# schematic.net
KiCad netlist of a schematic drawn in Altium Designer
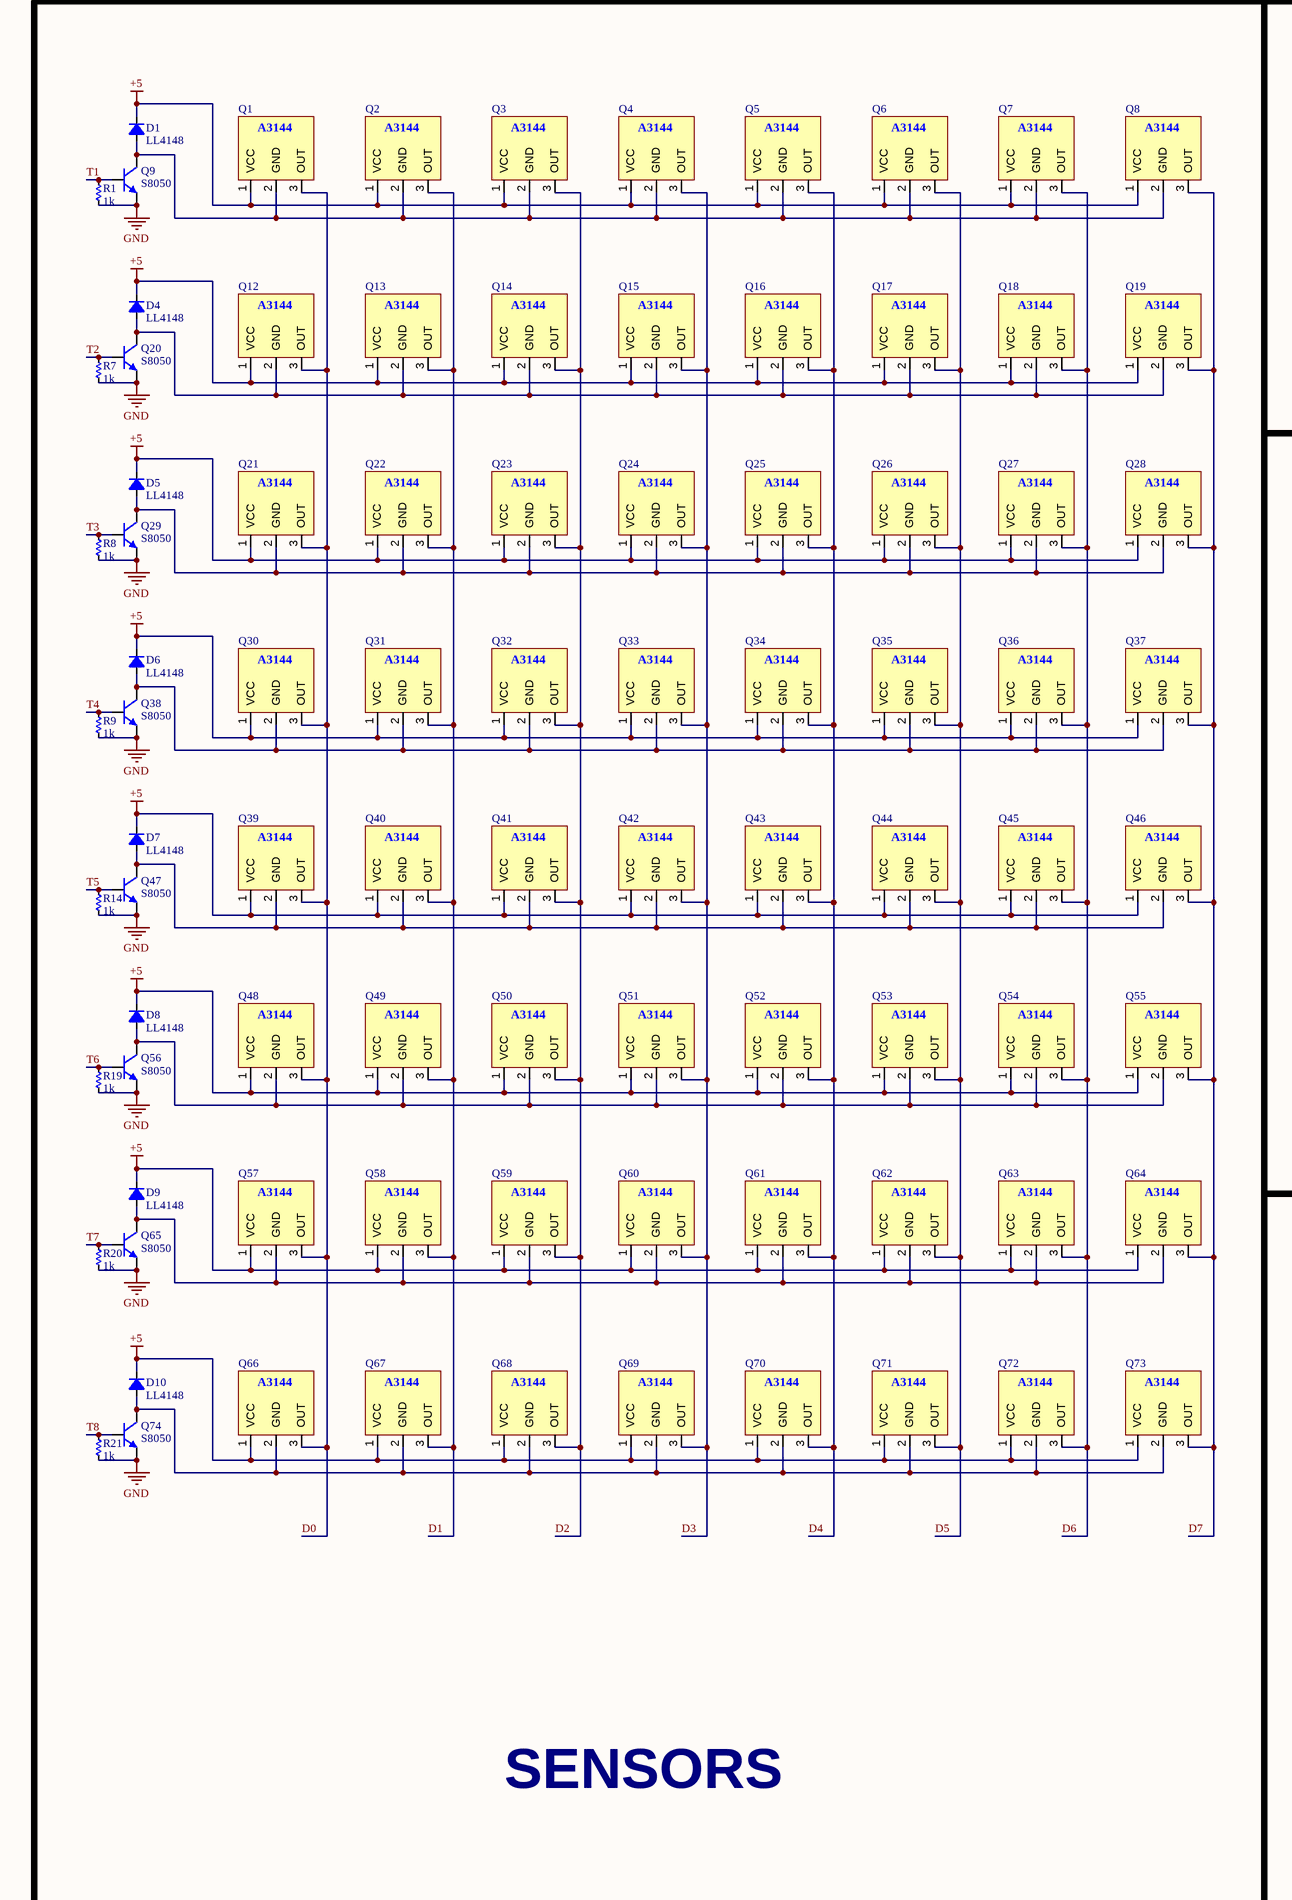
[diagram p0: schematic.SchDoc, left]
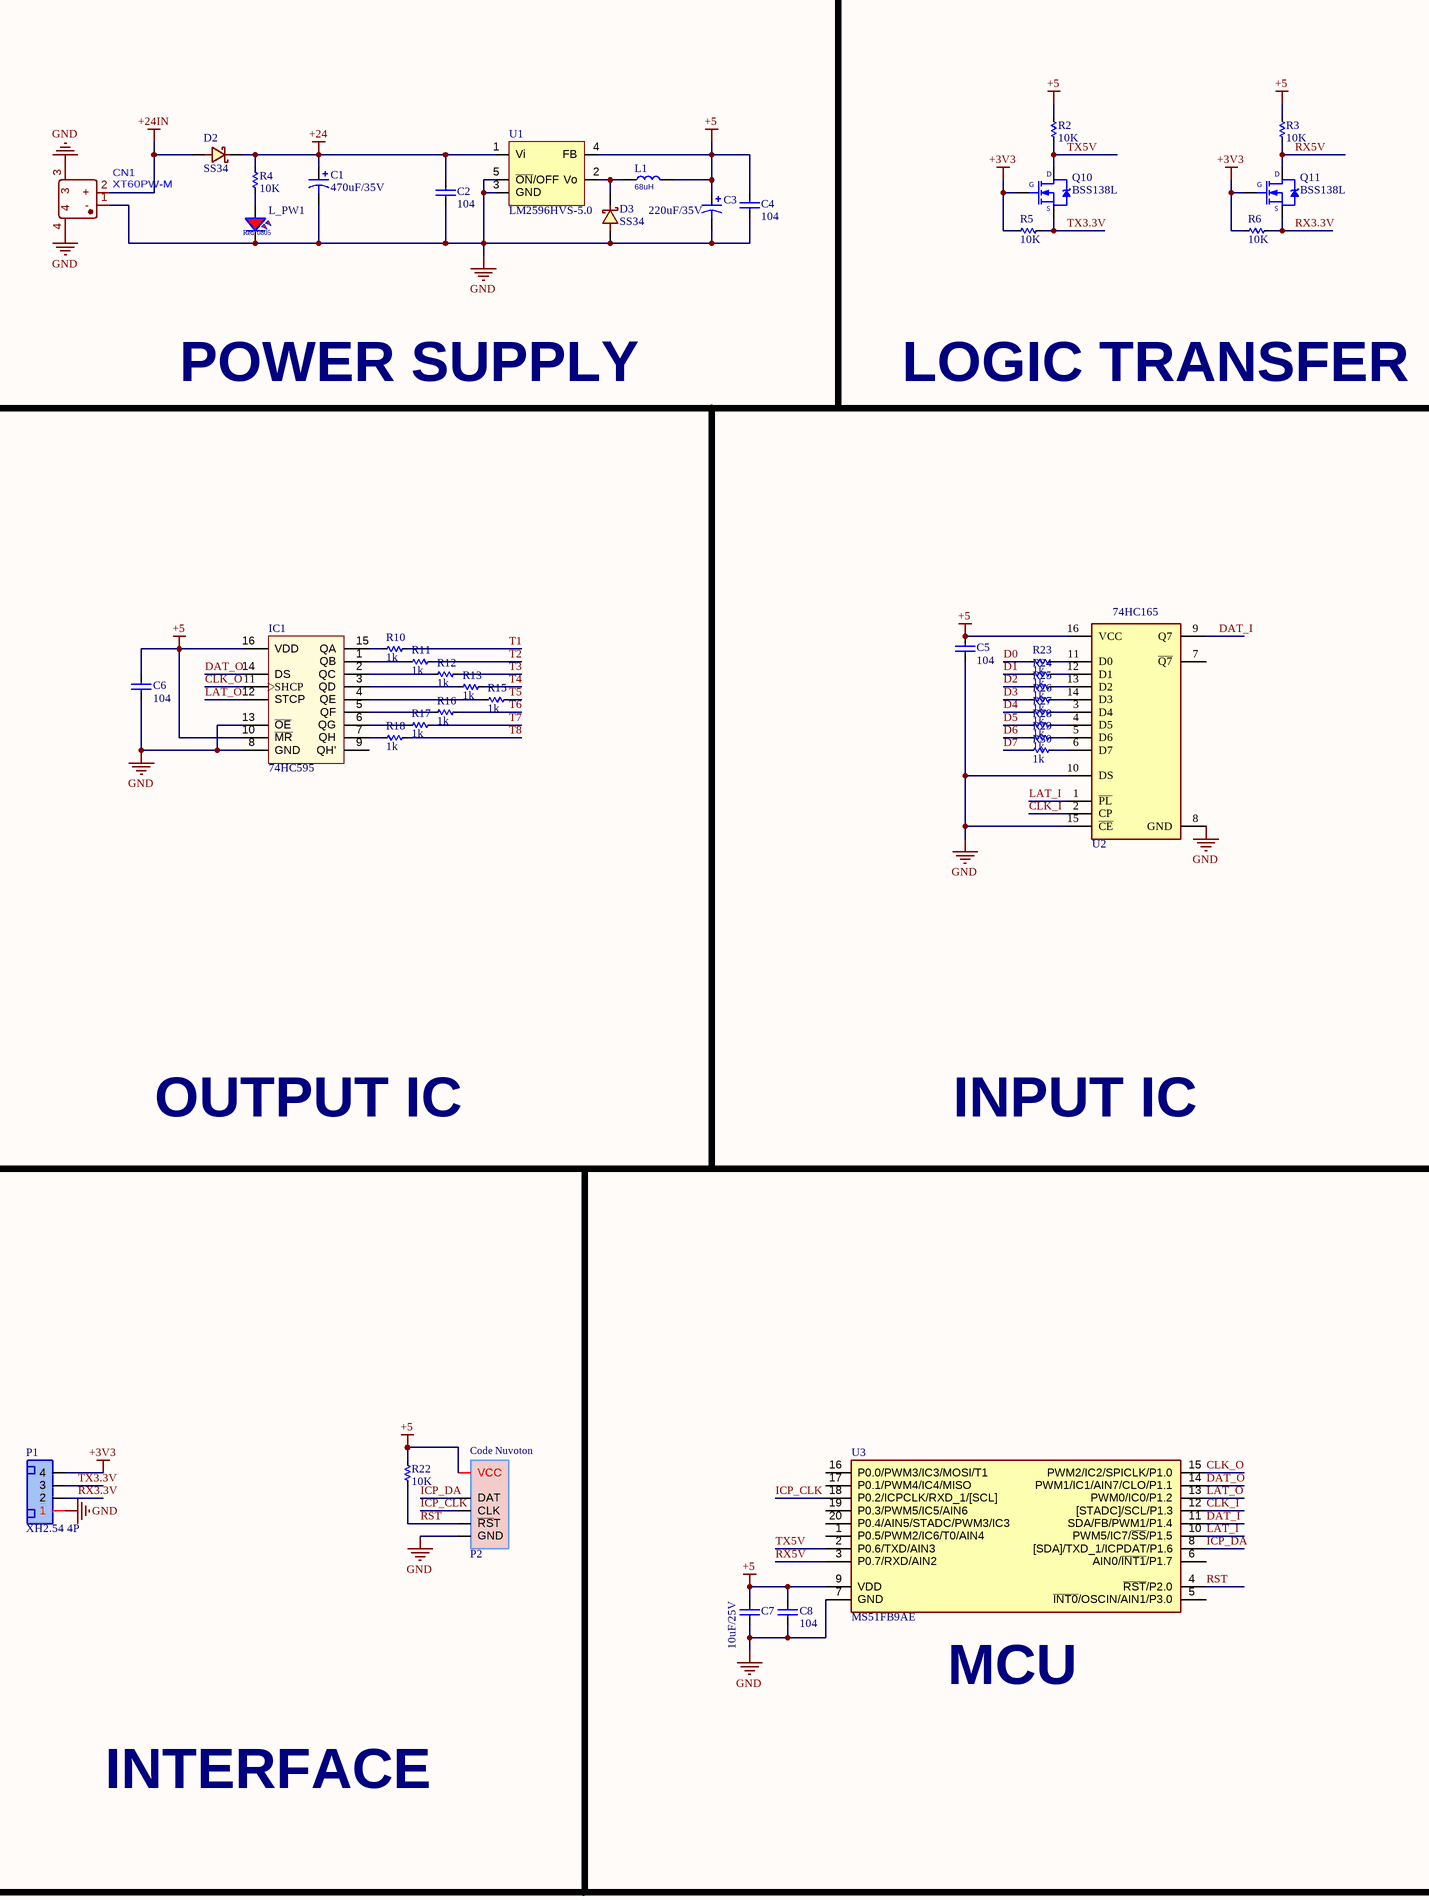
[diagram p1: schematic.SchDoc, right]

(export (version "E")
  (design (tool "Eeschema 10.0.6"))
  (components
    (comp (ref "C1")
      (value "470uF/35V")
      (footprint "C8X12mm")
      (description "Polarized Capacitor (Axial) 470uF 35V")
      (libsource (lib "RD Integrated_Library") (part "Cap Pol 470uF/35V"))
    )
    (comp (ref "C2")
      (value "104")
      (footprint "C_0805_SMD")
      (description "Cap SMD 0805 104-100nF-0.1uF 50V")
      (libsource (lib "RD Integrated_Library") (part "Cap 0805 104 100nF"))
    )
    (comp (ref "C3")
      (value "220uF/35V")
      (footprint "C8X12mm")
      (description "Polarized Capacitor (Axial) 220uF 35V")
      (libsource (lib "RD Integrated_Library") (part "Cap Pol 220uF/35V"))
    )
    (comp (ref "C4")
      (value "104")
      (footprint "C_0805_SMD")
      (description "Cap SMD 0805 104-100nF-0.1uF 50V")
      (libsource (lib "RD Integrated_Library") (part "Cap 0805 104 100nF"))
    )
    (comp (ref "C5")
      (value "104")
      (footprint "C_0805_SMD")
      (description "Cap SMD 0805 104-100nF-0.1uF 50V")
      (libsource (lib "RD Integrated_Library") (part "Cap 0805 104 100nF"))
    )
    (comp (ref "C6")
      (value "104")
      (footprint "C_0805_SMD")
      (description "Cap SMD 0805 104-100nF-0.1uF 50V")
      (libsource (lib "RD Integrated_Library") (part "Cap 0805 104 100nF"))
    )
    (comp (ref "C7")
      (value "10uF/25V")
      (footprint "C_0805_SMD")
      (description "Cap SMD 0805 10uF")
      (libsource (lib "RD Integrated_Library") (part "Cap 0805 10uF 25V"))
    )
    (comp (ref "C8")
      (value "104")
      (footprint "C_0805_SMD")
      (description "Cap SMD 0805 104-100nF-0.1uF 50V")
      (libsource (lib "RD Integrated_Library") (part "Cap 0805 104 100nF"))
    )
    (comp (ref "CN1")
      (value "XT60PW-M")
      (footprint "CONN-TH_XT60PW-M")
      (libsource (lib "Dlib") (part "XT60PW-M"))
    )
    (comp (ref "D1")
      (value "LL4148")
      (footprint "SOD80C_MFG")
      (description "0.2A, 100V, SOD80")
      (fields (field (name "DESIGNED BY") "Nhox"))
      (libsource (lib "RD Integrated_Library") (part "LL4148"))
    )
    (comp (ref "D2")
      (value "SS34")
      (footprint "D_SMA")
      (description "Surface-Mount Schottky Barrier Rectifier")
      (libsource (lib "RD Integrated_Library") (part "SS34-SMA"))
    )
    (comp (ref "D3")
      (value "SS34")
      (footprint "D_SMA")
      (description "Surface-Mount Schottky Barrier Rectifier")
      (libsource (lib "RD Integrated_Library") (part "SS34-SMA"))
    )
    (comp (ref "D4")
      (value "LL4148")
      (footprint "SOD80C_MFG")
      (description "0.2A, 100V, SOD80")
      (fields (field (name "DESIGNED BY") "Nhox"))
      (libsource (lib "RD Integrated_Library") (part "LL4148"))
    )
    (comp (ref "D5")
      (value "LL4148")
      (footprint "SOD80C_MFG")
      (description "0.2A, 100V, SOD80")
      (fields (field (name "DESIGNED BY") "Nhox"))
      (libsource (lib "RD Integrated_Library") (part "LL4148"))
    )
    (comp (ref "D6")
      (value "LL4148")
      (footprint "SOD80C_MFG")
      (description "0.2A, 100V, SOD80")
      (fields (field (name "DESIGNED BY") "Nhox"))
      (libsource (lib "RD Integrated_Library") (part "LL4148"))
    )
    (comp (ref "D7")
      (value "LL4148")
      (footprint "SOD80C_MFG")
      (description "0.2A, 100V, SOD80")
      (fields (field (name "DESIGNED BY") "Nhox"))
      (libsource (lib "RD Integrated_Library") (part "LL4148"))
    )
    (comp (ref "D8")
      (value "LL4148")
      (footprint "SOD80C_MFG")
      (description "0.2A, 100V, SOD80")
      (fields (field (name "DESIGNED BY") "Nhox"))
      (libsource (lib "RD Integrated_Library") (part "LL4148"))
    )
    (comp (ref "D9")
      (value "LL4148")
      (footprint "SOD80C_MFG")
      (description "0.2A, 100V, SOD80")
      (fields (field (name "DESIGNED BY") "Nhox"))
      (libsource (lib "RD Integrated_Library") (part "LL4148"))
    )
    (comp (ref "D10")
      (value "LL4148")
      (footprint "SOD80C_MFG")
      (description "0.2A, 100V, SOD80")
      (fields (field (name "DESIGNED BY") "Nhox"))
      (libsource (lib "RD Integrated_Library") (part "LL4148"))
    )
    (comp (ref "IC1")
      (value "74HC595")
      (footprint "SO_16")
      (description "Shift Register Single 8-Bit Serial to Serial/Parallel 16-Pin SOIC T/R")
      (fields (field (name "DESIGNED BY") "nhox"))
      (libsource (lib "RD Integrated_Library") (part "74HC595 SMD SO16"))
    )
    (comp (ref "L1")
      (value "68uH")
      (footprint "CDRH127")
      (description "CDRH127 Cuộn Cảm Dán SMD 1280-680 68uH 3.2A")
      (libsource (lib "RD Integrated_Library") (part "IND CDRH127 1280-680 68uH"))
    )
    (comp (ref "L_PW1")
      (value "LED RED")
      (footprint "LED 0805 Red")
      (description "LED 0805 SMD RED")
      (fields (field (name "DESIGNED BY") "TranLuyen"))
      (libsource (lib "RD Integrated_Library") (part "LED 0805 RED"))
    )
    (comp (ref "P1")
      (value "XH2.54 4P")
      (footprint "XH2.54_4P_RA")
      (description "XH2.54 RA")
      (libsource (lib "RD Integrated_Library") (part "XH2.54_4P_RA"))
    )
    (comp (ref "P2")
      (value "Nuvoton")
      (footprint "Header Code Nuvoton 2.54 6P")
      (description "Header 6-5Pin")
      (libsource (lib "RD Integrated_Library") (part "Header Code Nuvoton"))
    )
    (comp (ref "Q1")
      (value "A3144")
      (footprint "QTO-92")
      (description "Sensitive Hall Effect Switches for High-Temperature Operation 4.5-24V")
      (libsource (lib "RD Integrated_Library") (part "hall sensor A3144"))
    )
    (comp (ref "Q2")
      (value "A3144")
      (footprint "QTO-92")
      (description "Sensitive Hall Effect Switches for High-Temperature Operation 4.5-24V")
      (libsource (lib "RD Integrated_Library") (part "hall sensor A3144"))
    )
    (comp (ref "Q3")
      (value "A3144")
      (footprint "QTO-92")
      (description "Sensitive Hall Effect Switches for High-Temperature Operation 4.5-24V")
      (libsource (lib "RD Integrated_Library") (part "hall sensor A3144"))
    )
    (comp (ref "Q4")
      (value "A3144")
      (footprint "QTO-92")
      (description "Sensitive Hall Effect Switches for High-Temperature Operation 4.5-24V")
      (libsource (lib "RD Integrated_Library") (part "hall sensor A3144"))
    )
    (comp (ref "Q5")
      (value "A3144")
      (footprint "QTO-92")
      (description "Sensitive Hall Effect Switches for High-Temperature Operation 4.5-24V")
      (libsource (lib "RD Integrated_Library") (part "hall sensor A3144"))
    )
    (comp (ref "Q6")
      (value "A3144")
      (footprint "QTO-92")
      (description "Sensitive Hall Effect Switches for High-Temperature Operation 4.5-24V")
      (libsource (lib "RD Integrated_Library") (part "hall sensor A3144"))
    )
    (comp (ref "Q7")
      (value "A3144")
      (footprint "QTO-92")
      (description "Sensitive Hall Effect Switches for High-Temperature Operation 4.5-24V")
      (libsource (lib "RD Integrated_Library") (part "hall sensor A3144"))
    )
    (comp (ref "Q8")
      (value "A3144")
      (footprint "QTO-92")
      (description "Sensitive Hall Effect Switches for High-Temperature Operation 4.5-24V")
      (libsource (lib "RD Integrated_Library") (part "hall sensor A3144"))
    )
    (comp (ref "Q9")
      (value "S8050")
      (footprint "SOT23_N NXP")
      (description "J3Y-NPN SMD Transistor SOT23")
      (libsource (lib "RD Integrated_Library") (part "S8050 SOT-23"))
    )
    (comp (ref "Q10")
      (value "BSS138L")
      (footprint "SOT23_N NXP")
      (description "Power MOSFET 200 mA, 50V, N−Channel SOT23")
      (libsource (lib "RD Integrated_Library") (part "BSS138L SOT23"))
    )
    (comp (ref "Q11")
      (value "BSS138L")
      (footprint "SOT23_N NXP")
      (description "Power MOSFET 200 mA, 50V, N−Channel SOT23")
      (libsource (lib "RD Integrated_Library") (part "BSS138L SOT23"))
    )
    (comp (ref "Q12")
      (value "A3144")
      (footprint "QTO-92")
      (description "Sensitive Hall Effect Switches for High-Temperature Operation 4.5-24V")
      (libsource (lib "RD Integrated_Library") (part "hall sensor A3144"))
    )
    (comp (ref "Q13")
      (value "A3144")
      (footprint "QTO-92")
      (description "Sensitive Hall Effect Switches for High-Temperature Operation 4.5-24V")
      (libsource (lib "RD Integrated_Library") (part "hall sensor A3144"))
    )
    (comp (ref "Q14")
      (value "A3144")
      (footprint "QTO-92")
      (description "Sensitive Hall Effect Switches for High-Temperature Operation 4.5-24V")
      (libsource (lib "RD Integrated_Library") (part "hall sensor A3144"))
    )
    (comp (ref "Q15")
      (value "A3144")
      (footprint "QTO-92")
      (description "Sensitive Hall Effect Switches for High-Temperature Operation 4.5-24V")
      (libsource (lib "RD Integrated_Library") (part "hall sensor A3144"))
    )
    (comp (ref "Q16")
      (value "A3144")
      (footprint "QTO-92")
      (description "Sensitive Hall Effect Switches for High-Temperature Operation 4.5-24V")
      (libsource (lib "RD Integrated_Library") (part "hall sensor A3144"))
    )
    (comp (ref "Q17")
      (value "A3144")
      (footprint "QTO-92")
      (description "Sensitive Hall Effect Switches for High-Temperature Operation 4.5-24V")
      (libsource (lib "RD Integrated_Library") (part "hall sensor A3144"))
    )
    (comp (ref "Q18")
      (value "A3144")
      (footprint "QTO-92")
      (description "Sensitive Hall Effect Switches for High-Temperature Operation 4.5-24V")
      (libsource (lib "RD Integrated_Library") (part "hall sensor A3144"))
    )
    (comp (ref "Q19")
      (value "A3144")
      (footprint "QTO-92")
      (description "Sensitive Hall Effect Switches for High-Temperature Operation 4.5-24V")
      (libsource (lib "RD Integrated_Library") (part "hall sensor A3144"))
    )
    (comp (ref "Q20")
      (value "S8050")
      (footprint "SOT23_N NXP")
      (description "J3Y-NPN SMD Transistor SOT23")
      (libsource (lib "RD Integrated_Library") (part "S8050 SOT-23"))
    )
    (comp (ref "Q21")
      (value "A3144")
      (footprint "QTO-92")
      (description "Sensitive Hall Effect Switches for High-Temperature Operation 4.5-24V")
      (libsource (lib "RD Integrated_Library") (part "hall sensor A3144"))
    )
    (comp (ref "Q22")
      (value "A3144")
      (footprint "QTO-92")
      (description "Sensitive Hall Effect Switches for High-Temperature Operation 4.5-24V")
      (libsource (lib "RD Integrated_Library") (part "hall sensor A3144"))
    )
    (comp (ref "Q23")
      (value "A3144")
      (footprint "QTO-92")
      (description "Sensitive Hall Effect Switches for High-Temperature Operation 4.5-24V")
      (libsource (lib "RD Integrated_Library") (part "hall sensor A3144"))
    )
    (comp (ref "Q24")
      (value "A3144")
      (footprint "QTO-92")
      (description "Sensitive Hall Effect Switches for High-Temperature Operation 4.5-24V")
      (libsource (lib "RD Integrated_Library") (part "hall sensor A3144"))
    )
    (comp (ref "Q25")
      (value "A3144")
      (footprint "QTO-92")
      (description "Sensitive Hall Effect Switches for High-Temperature Operation 4.5-24V")
      (libsource (lib "RD Integrated_Library") (part "hall sensor A3144"))
    )
    (comp (ref "Q26")
      (value "A3144")
      (footprint "QTO-92")
      (description "Sensitive Hall Effect Switches for High-Temperature Operation 4.5-24V")
      (libsource (lib "RD Integrated_Library") (part "hall sensor A3144"))
    )
    (comp (ref "Q27")
      (value "A3144")
      (footprint "QTO-92")
      (description "Sensitive Hall Effect Switches for High-Temperature Operation 4.5-24V")
      (libsource (lib "RD Integrated_Library") (part "hall sensor A3144"))
    )
    (comp (ref "Q28")
      (value "A3144")
      (footprint "QTO-92")
      (description "Sensitive Hall Effect Switches for High-Temperature Operation 4.5-24V")
      (libsource (lib "RD Integrated_Library") (part "hall sensor A3144"))
    )
    (comp (ref "Q29")
      (value "S8050")
      (footprint "SOT23_N NXP")
      (description "J3Y-NPN SMD Transistor SOT23")
      (libsource (lib "RD Integrated_Library") (part "S8050 SOT-23"))
    )
    (comp (ref "Q30")
      (value "A3144")
      (footprint "QTO-92")
      (description "Sensitive Hall Effect Switches for High-Temperature Operation 4.5-24V")
      (libsource (lib "RD Integrated_Library") (part "hall sensor A3144"))
    )
    (comp (ref "Q31")
      (value "A3144")
      (footprint "QTO-92")
      (description "Sensitive Hall Effect Switches for High-Temperature Operation 4.5-24V")
      (libsource (lib "RD Integrated_Library") (part "hall sensor A3144"))
    )
    (comp (ref "Q32")
      (value "A3144")
      (footprint "QTO-92")
      (description "Sensitive Hall Effect Switches for High-Temperature Operation 4.5-24V")
      (libsource (lib "RD Integrated_Library") (part "hall sensor A3144"))
    )
    (comp (ref "Q33")
      (value "A3144")
      (footprint "QTO-92")
      (description "Sensitive Hall Effect Switches for High-Temperature Operation 4.5-24V")
      (libsource (lib "RD Integrated_Library") (part "hall sensor A3144"))
    )
    (comp (ref "Q34")
      (value "A3144")
      (footprint "QTO-92")
      (description "Sensitive Hall Effect Switches for High-Temperature Operation 4.5-24V")
      (libsource (lib "RD Integrated_Library") (part "hall sensor A3144"))
    )
    (comp (ref "Q35")
      (value "A3144")
      (footprint "QTO-92")
      (description "Sensitive Hall Effect Switches for High-Temperature Operation 4.5-24V")
      (libsource (lib "RD Integrated_Library") (part "hall sensor A3144"))
    )
    (comp (ref "Q36")
      (value "A3144")
      (footprint "QTO-92")
      (description "Sensitive Hall Effect Switches for High-Temperature Operation 4.5-24V")
      (libsource (lib "RD Integrated_Library") (part "hall sensor A3144"))
    )
    (comp (ref "Q37")
      (value "A3144")
      (footprint "QTO-92")
      (description "Sensitive Hall Effect Switches for High-Temperature Operation 4.5-24V")
      (libsource (lib "RD Integrated_Library") (part "hall sensor A3144"))
    )
    (comp (ref "Q38")
      (value "S8050")
      (footprint "SOT23_N NXP")
      (description "J3Y-NPN SMD Transistor SOT23")
      (libsource (lib "RD Integrated_Library") (part "S8050 SOT-23"))
    )
    (comp (ref "Q39")
      (value "A3144")
      (footprint "QTO-92")
      (description "Sensitive Hall Effect Switches for High-Temperature Operation 4.5-24V")
      (libsource (lib "RD Integrated_Library") (part "hall sensor A3144"))
    )
    (comp (ref "Q40")
      (value "A3144")
      (footprint "QTO-92")
      (description "Sensitive Hall Effect Switches for High-Temperature Operation 4.5-24V")
      (libsource (lib "RD Integrated_Library") (part "hall sensor A3144"))
    )
    (comp (ref "Q41")
      (value "A3144")
      (footprint "QTO-92")
      (description "Sensitive Hall Effect Switches for High-Temperature Operation 4.5-24V")
      (libsource (lib "RD Integrated_Library") (part "hall sensor A3144"))
    )
    (comp (ref "Q42")
      (value "A3144")
      (footprint "QTO-92")
      (description "Sensitive Hall Effect Switches for High-Temperature Operation 4.5-24V")
      (libsource (lib "RD Integrated_Library") (part "hall sensor A3144"))
    )
    (comp (ref "Q43")
      (value "A3144")
      (footprint "QTO-92")
      (description "Sensitive Hall Effect Switches for High-Temperature Operation 4.5-24V")
      (libsource (lib "RD Integrated_Library") (part "hall sensor A3144"))
    )
    (comp (ref "Q44")
      (value "A3144")
      (footprint "QTO-92")
      (description "Sensitive Hall Effect Switches for High-Temperature Operation 4.5-24V")
      (libsource (lib "RD Integrated_Library") (part "hall sensor A3144"))
    )
    (comp (ref "Q45")
      (value "A3144")
      (footprint "QTO-92")
      (description "Sensitive Hall Effect Switches for High-Temperature Operation 4.5-24V")
      (libsource (lib "RD Integrated_Library") (part "hall sensor A3144"))
    )
    (comp (ref "Q46")
      (value "A3144")
      (footprint "QTO-92")
      (description "Sensitive Hall Effect Switches for High-Temperature Operation 4.5-24V")
      (libsource (lib "RD Integrated_Library") (part "hall sensor A3144"))
    )
    (comp (ref "Q47")
      (value "S8050")
      (footprint "SOT23_N NXP")
      (description "J3Y-NPN SMD Transistor SOT23")
      (libsource (lib "RD Integrated_Library") (part "S8050 SOT-23"))
    )
    (comp (ref "Q48")
      (value "A3144")
      (footprint "QTO-92")
      (description "Sensitive Hall Effect Switches for High-Temperature Operation 4.5-24V")
      (libsource (lib "RD Integrated_Library") (part "hall sensor A3144"))
    )
    (comp (ref "Q49")
      (value "A3144")
      (footprint "QTO-92")
      (description "Sensitive Hall Effect Switches for High-Temperature Operation 4.5-24V")
      (libsource (lib "RD Integrated_Library") (part "hall sensor A3144"))
    )
    (comp (ref "Q50")
      (value "A3144")
      (footprint "QTO-92")
      (description "Sensitive Hall Effect Switches for High-Temperature Operation 4.5-24V")
      (libsource (lib "RD Integrated_Library") (part "hall sensor A3144"))
    )
    (comp (ref "Q51")
      (value "A3144")
      (footprint "QTO-92")
      (description "Sensitive Hall Effect Switches for High-Temperature Operation 4.5-24V")
      (libsource (lib "RD Integrated_Library") (part "hall sensor A3144"))
    )
    (comp (ref "Q52")
      (value "A3144")
      (footprint "QTO-92")
      (description "Sensitive Hall Effect Switches for High-Temperature Operation 4.5-24V")
      (libsource (lib "RD Integrated_Library") (part "hall sensor A3144"))
    )
    (comp (ref "Q53")
      (value "A3144")
      (footprint "QTO-92")
      (description "Sensitive Hall Effect Switches for High-Temperature Operation 4.5-24V")
      (libsource (lib "RD Integrated_Library") (part "hall sensor A3144"))
    )
    (comp (ref "Q54")
      (value "A3144")
      (footprint "QTO-92")
      (description "Sensitive Hall Effect Switches for High-Temperature Operation 4.5-24V")
      (libsource (lib "RD Integrated_Library") (part "hall sensor A3144"))
    )
    (comp (ref "Q55")
      (value "A3144")
      (footprint "QTO-92")
      (description "Sensitive Hall Effect Switches for High-Temperature Operation 4.5-24V")
      (libsource (lib "RD Integrated_Library") (part "hall sensor A3144"))
    )
    (comp (ref "Q56")
      (value "S8050")
      (footprint "SOT23_N NXP")
      (description "J3Y-NPN SMD Transistor SOT23")
      (libsource (lib "RD Integrated_Library") (part "S8050 SOT-23"))
    )
    (comp (ref "Q57")
      (value "A3144")
      (footprint "QTO-92")
      (description "Sensitive Hall Effect Switches for High-Temperature Operation 4.5-24V")
      (libsource (lib "RD Integrated_Library") (part "hall sensor A3144"))
    )
    (comp (ref "Q58")
      (value "A3144")
      (footprint "QTO-92")
      (description "Sensitive Hall Effect Switches for High-Temperature Operation 4.5-24V")
      (libsource (lib "RD Integrated_Library") (part "hall sensor A3144"))
    )
    (comp (ref "Q59")
      (value "A3144")
      (footprint "QTO-92")
      (description "Sensitive Hall Effect Switches for High-Temperature Operation 4.5-24V")
      (libsource (lib "RD Integrated_Library") (part "hall sensor A3144"))
    )
    (comp (ref "Q60")
      (value "A3144")
      (footprint "QTO-92")
      (description "Sensitive Hall Effect Switches for High-Temperature Operation 4.5-24V")
      (libsource (lib "RD Integrated_Library") (part "hall sensor A3144"))
    )
    (comp (ref "Q61")
      (value "A3144")
      (footprint "QTO-92")
      (description "Sensitive Hall Effect Switches for High-Temperature Operation 4.5-24V")
      (libsource (lib "RD Integrated_Library") (part "hall sensor A3144"))
    )
    (comp (ref "Q62")
      (value "A3144")
      (footprint "QTO-92")
      (description "Sensitive Hall Effect Switches for High-Temperature Operation 4.5-24V")
      (libsource (lib "RD Integrated_Library") (part "hall sensor A3144"))
    )
    (comp (ref "Q63")
      (value "A3144")
      (footprint "QTO-92")
      (description "Sensitive Hall Effect Switches for High-Temperature Operation 4.5-24V")
      (libsource (lib "RD Integrated_Library") (part "hall sensor A3144"))
    )
    (comp (ref "Q64")
      (value "A3144")
      (footprint "QTO-92")
      (description "Sensitive Hall Effect Switches for High-Temperature Operation 4.5-24V")
      (libsource (lib "RD Integrated_Library") (part "hall sensor A3144"))
    )
    (comp (ref "Q65")
      (value "S8050")
      (footprint "SOT23_N NXP")
      (description "J3Y-NPN SMD Transistor SOT23")
      (libsource (lib "RD Integrated_Library") (part "S8050 SOT-23"))
    )
    (comp (ref "Q66")
      (value "A3144")
      (footprint "QTO-92")
      (description "Sensitive Hall Effect Switches for High-Temperature Operation 4.5-24V")
      (libsource (lib "RD Integrated_Library") (part "hall sensor A3144"))
    )
    (comp (ref "Q67")
      (value "A3144")
      (footprint "QTO-92")
      (description "Sensitive Hall Effect Switches for High-Temperature Operation 4.5-24V")
      (libsource (lib "RD Integrated_Library") (part "hall sensor A3144"))
    )
    (comp (ref "Q68")
      (value "A3144")
      (footprint "QTO-92")
      (description "Sensitive Hall Effect Switches for High-Temperature Operation 4.5-24V")
      (libsource (lib "RD Integrated_Library") (part "hall sensor A3144"))
    )
    (comp (ref "Q69")
      (value "A3144")
      (footprint "QTO-92")
      (description "Sensitive Hall Effect Switches for High-Temperature Operation 4.5-24V")
      (libsource (lib "RD Integrated_Library") (part "hall sensor A3144"))
    )
    (comp (ref "Q70")
      (value "A3144")
      (footprint "QTO-92")
      (description "Sensitive Hall Effect Switches for High-Temperature Operation 4.5-24V")
      (libsource (lib "RD Integrated_Library") (part "hall sensor A3144"))
    )
    (comp (ref "Q71")
      (value "A3144")
      (footprint "QTO-92")
      (description "Sensitive Hall Effect Switches for High-Temperature Operation 4.5-24V")
      (libsource (lib "RD Integrated_Library") (part "hall sensor A3144"))
    )
    (comp (ref "Q72")
      (value "A3144")
      (footprint "QTO-92")
      (description "Sensitive Hall Effect Switches for High-Temperature Operation 4.5-24V")
      (libsource (lib "RD Integrated_Library") (part "hall sensor A3144"))
    )
    (comp (ref "Q73")
      (value "A3144")
      (footprint "QTO-92")
      (description "Sensitive Hall Effect Switches for High-Temperature Operation 4.5-24V")
      (libsource (lib "RD Integrated_Library") (part "hall sensor A3144"))
    )
    (comp (ref "Q74")
      (value "S8050")
      (footprint "SOT23_N NXP")
      (description "J3Y-NPN SMD Transistor SOT23")
      (libsource (lib "RD Integrated_Library") (part "S8050 SOT-23"))
    )
    (comp (ref "R1")
      (value "1k")
      (footprint "RES-SMD-0805")
      (description "Resistor SMD 0805")
      (libsource (lib "RD Integrated_Library") (part "Res 1k 0805"))
    )
    (comp (ref "R2")
      (value "10K")
      (footprint "RES-SMD-0805")
      (description "Resistor SMD 0805")
      (libsource (lib "RD Integrated_Library") (part "Res 10k 0805"))
    )
    (comp (ref "R3")
      (value "10K")
      (footprint "RES-SMD-0805")
      (description "Resistor SMD 0805")
      (libsource (lib "RD Integrated_Library") (part "Res 10k 0805"))
    )
    (comp (ref "R4")
      (value "10K")
      (footprint "RES-SMD-0805")
      (description "Resistor SMD 0805")
      (libsource (lib "RD Integrated_Library") (part "Res 10k 0805"))
    )
    (comp (ref "R5")
      (value "10K")
      (footprint "RES-SMD-0805")
      (description "Resistor SMD 0805")
      (libsource (lib "RD Integrated_Library") (part "Res 10k 0805"))
    )
    (comp (ref "R6")
      (value "10K")
      (footprint "RES-SMD-0805")
      (description "Resistor SMD 0805")
      (libsource (lib "RD Integrated_Library") (part "Res 10k 0805"))
    )
    (comp (ref "R7")
      (value "1k")
      (footprint "RES-SMD-0805")
      (description "Resistor SMD 0805")
      (libsource (lib "RD Integrated_Library") (part "Res 1k 0805"))
    )
    (comp (ref "R8")
      (value "1k")
      (footprint "RES-SMD-0805")
      (description "Resistor SMD 0805")
      (libsource (lib "RD Integrated_Library") (part "Res 1k 0805"))
    )
    (comp (ref "R9")
      (value "1k")
      (footprint "RES-SMD-0805")
      (description "Resistor SMD 0805")
      (libsource (lib "RD Integrated_Library") (part "Res 1k 0805"))
    )
    (comp (ref "R10")
      (value "1k")
      (footprint "RES-SMD-0805")
      (description "Resistor SMD 0805")
      (libsource (lib "RD Integrated_Library") (part "Res 1k 0805"))
    )
    (comp (ref "R11")
      (value "1k")
      (footprint "RES-SMD-0805")
      (description "Resistor SMD 0805")
      (libsource (lib "RD Integrated_Library") (part "Res 1k 0805"))
    )
    (comp (ref "R12")
      (value "1k")
      (footprint "RES-SMD-0805")
      (description "Resistor SMD 0805")
      (libsource (lib "RD Integrated_Library") (part "Res 1k 0805"))
    )
    (comp (ref "R13")
      (value "1k")
      (footprint "RES-SMD-0805")
      (description "Resistor SMD 0805")
      (libsource (lib "RD Integrated_Library") (part "Res 1k 0805"))
    )
    (comp (ref "R14")
      (value "1k")
      (footprint "RES-SMD-0805")
      (description "Resistor SMD 0805")
      (libsource (lib "RD Integrated_Library") (part "Res 1k 0805"))
    )
    (comp (ref "R15")
      (value "1k")
      (footprint "RES-SMD-0805")
      (description "Resistor SMD 0805")
      (libsource (lib "RD Integrated_Library") (part "Res 1k 0805"))
    )
    (comp (ref "R16")
      (value "1k")
      (footprint "RES-SMD-0805")
      (description "Resistor SMD 0805")
      (libsource (lib "RD Integrated_Library") (part "Res 1k 0805"))
    )
    (comp (ref "R17")
      (value "1k")
      (footprint "RES-SMD-0805")
      (description "Resistor SMD 0805")
      (libsource (lib "RD Integrated_Library") (part "Res 1k 0805"))
    )
    (comp (ref "R18")
      (value "1k")
      (footprint "RES-SMD-0805")
      (description "Resistor SMD 0805")
      (libsource (lib "RD Integrated_Library") (part "Res 1k 0805"))
    )
    (comp (ref "R19")
      (value "1k")
      (footprint "RES-SMD-0805")
      (description "Resistor SMD 0805")
      (libsource (lib "RD Integrated_Library") (part "Res 1k 0805"))
    )
    (comp (ref "R20")
      (value "1k")
      (footprint "RES-SMD-0805")
      (description "Resistor SMD 0805")
      (libsource (lib "RD Integrated_Library") (part "Res 1k 0805"))
    )
    (comp (ref "R21")
      (value "1k")
      (footprint "RES-SMD-0805")
      (description "Resistor SMD 0805")
      (libsource (lib "RD Integrated_Library") (part "Res 1k 0805"))
    )
    (comp (ref "R22")
      (value "10K")
      (footprint "RES-SMD-0805")
      (description "Resistor SMD 0805")
      (libsource (lib "RD Integrated_Library") (part "Res 10k 0805"))
    )
    (comp (ref "R23")
      (value "1k")
      (footprint "RES-SMD-0805")
      (description "Resistor SMD 0805")
      (libsource (lib "RD Integrated_Library") (part "Res 1k 0805"))
    )
    (comp (ref "R24")
      (value "1k")
      (footprint "RES-SMD-0805")
      (description "Resistor SMD 0805")
      (libsource (lib "RD Integrated_Library") (part "Res 1k 0805"))
    )
    (comp (ref "R25")
      (value "1k")
      (footprint "RES-SMD-0805")
      (description "Resistor SMD 0805")
      (libsource (lib "RD Integrated_Library") (part "Res 1k 0805"))
    )
    (comp (ref "R26")
      (value "1k")
      (footprint "RES-SMD-0805")
      (description "Resistor SMD 0805")
      (libsource (lib "RD Integrated_Library") (part "Res 1k 0805"))
    )
    (comp (ref "R27")
      (value "1k")
      (footprint "RES-SMD-0805")
      (description "Resistor SMD 0805")
      (libsource (lib "RD Integrated_Library") (part "Res 1k 0805"))
    )
    (comp (ref "R28")
      (value "1k")
      (footprint "RES-SMD-0805")
      (description "Resistor SMD 0805")
      (libsource (lib "RD Integrated_Library") (part "Res 1k 0805"))
    )
    (comp (ref "R29")
      (value "1k")
      (footprint "RES-SMD-0805")
      (description "Resistor SMD 0805")
      (libsource (lib "RD Integrated_Library") (part "Res 1k 0805"))
    )
    (comp (ref "R30")
      (value "1k")
      (footprint "RES-SMD-0805")
      (description "Resistor SMD 0805")
      (libsource (lib "RD Integrated_Library") (part "Res 1k 0805"))
    )
    (comp (ref "U1")
      (value "LM2596HVS-5.0")
      (footprint "TO-263-5")
      (description "Vin 4.5-40VDC, Vout 5VDC, Iout MAX 3A")
      (libsource (lib "RD Integrated_Library") (part "LM2596HVS-5.0"))
    )
    (comp (ref "U2")
      (value "74HC165")
      (footprint "SO_16")
      (description "IC Shift Register 1 Element 8 Bit, Complementary 16-SOIC")
      (fields (field (name "DESIGNED BY") "nhox"))
      (libsource (lib "RD Integrated_Library") (part "74HC165-SOIC-16"))
    )
    (comp (ref "U3")
      (value "MS51FB9AE")
      (footprint "SOG65_20")
      (description "MS51FB9AE, ROM 16KB, RAM 256B + 1KB, SPROM 128B, 1T 8051-based CMOS up to 24Mhz")
      (fields (field (name "DESIGNED BY") "Nhox"))
      (libsource (lib "RD Integrated_Library") (part "MS51FB9AE"))
    )
  )
  (nets
    (net (code "1") (name "+3V3") (class "Default")
      (node (ref "P1") (pin "4") (pinfunction "4_4") (pintype "passive"))
      (node (ref "Q10") (pin "1") (pinfunction "G_1") (pintype "passive"))
      (node (ref "Q11") (pin "1") (pinfunction "G_1") (pintype "passive"))
      (node (ref "R5") (pin "2") (pinfunction "2_2") (pintype "passive"))
      (node (ref "R6") (pin "2") (pinfunction "2_2") (pintype "passive"))
    )
    (net (code "2") (name "+5") (class "Default")
      (node (ref "C3") (pin "1") (pinfunction "1_1") (pintype "passive"))
      (node (ref "C4") (pin "2") (pinfunction "2_2") (pintype "passive"))
      (node (ref "C5") (pin "2") (pinfunction "2_2") (pintype "passive"))
      (node (ref "C6") (pin "2") (pinfunction "2_2") (pintype "passive"))
      (node (ref "C7") (pin "1") (pinfunction "1_1") (pintype "passive"))
      (node (ref "C8") (pin "1") (pinfunction "1_1") (pintype "passive"))
      (node (ref "D1") (pin "1") (pinfunction "1_1") (pintype "passive"))
      (node (ref "D10") (pin "1") (pinfunction "1_1") (pintype "passive"))
      (node (ref "D4") (pin "1") (pinfunction "1_1") (pintype "passive"))
      (node (ref "D5") (pin "1") (pinfunction "1_1") (pintype "passive"))
      (node (ref "D6") (pin "1") (pinfunction "1_1") (pintype "passive"))
      (node (ref "D7") (pin "1") (pinfunction "1_1") (pintype "passive"))
      (node (ref "D8") (pin "1") (pinfunction "1_1") (pintype "passive"))
      (node (ref "D9") (pin "1") (pinfunction "1_1") (pintype "passive"))
      (node (ref "IC1") (pin "10") (pinfunction "~{MR}_10") (pintype "passive"))
      (node (ref "IC1") (pin "16") (pinfunction "VDD_16") (pintype "power_in"))
      (node (ref "L1") (pin "2") (pinfunction "2_2") (pintype "passive"))
      (node (ref "P2") (pin "1") (pinfunction "VCC_1") (pintype "passive"))
      (node (ref "Q1") (pin "1") (pinfunction "VCC_1") (pintype "passive"))
      (node (ref "Q12") (pin "1") (pinfunction "VCC_1") (pintype "passive"))
      (node (ref "Q13") (pin "1") (pinfunction "VCC_1") (pintype "passive"))
      (node (ref "Q14") (pin "1") (pinfunction "VCC_1") (pintype "passive"))
      (node (ref "Q15") (pin "1") (pinfunction "VCC_1") (pintype "passive"))
      (node (ref "Q16") (pin "1") (pinfunction "VCC_1") (pintype "passive"))
      (node (ref "Q17") (pin "1") (pinfunction "VCC_1") (pintype "passive"))
      (node (ref "Q18") (pin "1") (pinfunction "VCC_1") (pintype "passive"))
      (node (ref "Q19") (pin "1") (pinfunction "VCC_1") (pintype "passive"))
      (node (ref "Q2") (pin "1") (pinfunction "VCC_1") (pintype "passive"))
      (node (ref "Q21") (pin "1") (pinfunction "VCC_1") (pintype "passive"))
      (node (ref "Q22") (pin "1") (pinfunction "VCC_1") (pintype "passive"))
      (node (ref "Q23") (pin "1") (pinfunction "VCC_1") (pintype "passive"))
      (node (ref "Q24") (pin "1") (pinfunction "VCC_1") (pintype "passive"))
      (node (ref "Q25") (pin "1") (pinfunction "VCC_1") (pintype "passive"))
      (node (ref "Q26") (pin "1") (pinfunction "VCC_1") (pintype "passive"))
      (node (ref "Q27") (pin "1") (pinfunction "VCC_1") (pintype "passive"))
      (node (ref "Q28") (pin "1") (pinfunction "VCC_1") (pintype "passive"))
      (node (ref "Q3") (pin "1") (pinfunction "VCC_1") (pintype "passive"))
      (node (ref "Q30") (pin "1") (pinfunction "VCC_1") (pintype "passive"))
      (node (ref "Q31") (pin "1") (pinfunction "VCC_1") (pintype "passive"))
      (node (ref "Q32") (pin "1") (pinfunction "VCC_1") (pintype "passive"))
      (node (ref "Q33") (pin "1") (pinfunction "VCC_1") (pintype "passive"))
      (node (ref "Q34") (pin "1") (pinfunction "VCC_1") (pintype "passive"))
      (node (ref "Q35") (pin "1") (pinfunction "VCC_1") (pintype "passive"))
      (node (ref "Q36") (pin "1") (pinfunction "VCC_1") (pintype "passive"))
      (node (ref "Q37") (pin "1") (pinfunction "VCC_1") (pintype "passive"))
      (node (ref "Q39") (pin "1") (pinfunction "VCC_1") (pintype "passive"))
      (node (ref "Q4") (pin "1") (pinfunction "VCC_1") (pintype "passive"))
      (node (ref "Q40") (pin "1") (pinfunction "VCC_1") (pintype "passive"))
      (node (ref "Q41") (pin "1") (pinfunction "VCC_1") (pintype "passive"))
      (node (ref "Q42") (pin "1") (pinfunction "VCC_1") (pintype "passive"))
      (node (ref "Q43") (pin "1") (pinfunction "VCC_1") (pintype "passive"))
      (node (ref "Q44") (pin "1") (pinfunction "VCC_1") (pintype "passive"))
      (node (ref "Q45") (pin "1") (pinfunction "VCC_1") (pintype "passive"))
      (node (ref "Q46") (pin "1") (pinfunction "VCC_1") (pintype "passive"))
      (node (ref "Q48") (pin "1") (pinfunction "VCC_1") (pintype "passive"))
      (node (ref "Q49") (pin "1") (pinfunction "VCC_1") (pintype "passive"))
      (node (ref "Q5") (pin "1") (pinfunction "VCC_1") (pintype "passive"))
      (node (ref "Q50") (pin "1") (pinfunction "VCC_1") (pintype "passive"))
      (node (ref "Q51") (pin "1") (pinfunction "VCC_1") (pintype "passive"))
      (node (ref "Q52") (pin "1") (pinfunction "VCC_1") (pintype "passive"))
      (node (ref "Q53") (pin "1") (pinfunction "VCC_1") (pintype "passive"))
      (node (ref "Q54") (pin "1") (pinfunction "VCC_1") (pintype "passive"))
      (node (ref "Q55") (pin "1") (pinfunction "VCC_1") (pintype "passive"))
      (node (ref "Q57") (pin "1") (pinfunction "VCC_1") (pintype "passive"))
      (node (ref "Q58") (pin "1") (pinfunction "VCC_1") (pintype "passive"))
      (node (ref "Q59") (pin "1") (pinfunction "VCC_1") (pintype "passive"))
      (node (ref "Q6") (pin "1") (pinfunction "VCC_1") (pintype "passive"))
      (node (ref "Q60") (pin "1") (pinfunction "VCC_1") (pintype "passive"))
      (node (ref "Q61") (pin "1") (pinfunction "VCC_1") (pintype "passive"))
      (node (ref "Q62") (pin "1") (pinfunction "VCC_1") (pintype "passive"))
      (node (ref "Q63") (pin "1") (pinfunction "VCC_1") (pintype "passive"))
      (node (ref "Q64") (pin "1") (pinfunction "VCC_1") (pintype "passive"))
      (node (ref "Q66") (pin "1") (pinfunction "VCC_1") (pintype "passive"))
      (node (ref "Q67") (pin "1") (pinfunction "VCC_1") (pintype "passive"))
      (node (ref "Q68") (pin "1") (pinfunction "VCC_1") (pintype "passive"))
      (node (ref "Q69") (pin "1") (pinfunction "VCC_1") (pintype "passive"))
      (node (ref "Q7") (pin "1") (pinfunction "VCC_1") (pintype "passive"))
      (node (ref "Q70") (pin "1") (pinfunction "VCC_1") (pintype "passive"))
      (node (ref "Q71") (pin "1") (pinfunction "VCC_1") (pintype "passive"))
      (node (ref "Q72") (pin "1") (pinfunction "VCC_1") (pintype "passive"))
      (node (ref "Q73") (pin "1") (pinfunction "VCC_1") (pintype "passive"))
      (node (ref "Q8") (pin "1") (pinfunction "VCC_1") (pintype "passive"))
      (node (ref "R2") (pin "2") (pinfunction "2_2") (pintype "passive"))
      (node (ref "R22") (pin "1") (pinfunction "1_1") (pintype "passive"))
      (node (ref "R3") (pin "2") (pinfunction "2_2") (pintype "passive"))
      (node (ref "U1") (pin "4") (pinfunction "FB_4") (pintype "passive"))
      (node (ref "U2") (pin "16") (pinfunction "VCC_16") (pintype "power_in"))
      (node (ref "U3") (pin "9") (pinfunction "VDD_9") (pintype "passive"))
    )
    (net (code "3") (name "+24") (class "Default")
      (node (ref "C1") (pin "1") (pinfunction "1_1") (pintype "passive"))
      (node (ref "C2") (pin "2") (pinfunction "2_2") (pintype "passive"))
      (node (ref "D2") (pin "2") (pinfunction "K_2") (pintype "passive"))
      (node (ref "R4") (pin "1") (pinfunction "1_1") (pintype "passive"))
      (node (ref "U1") (pin "1") (pinfunction "Vi_1") (pintype "passive"))
    )
    (net (code "4") (name "+24IN") (class "Default")
      (node (ref "CN1") (pin "2") (pinfunction "+_2") (pintype "passive"))
      (node (ref "D2") (pin "1") (pinfunction "A_1") (pintype "passive"))
    )
    (net (code "5") (name "/CLK_I") (class "Default")
      (node (ref "U2") (pin "2") (pinfunction "CP_2") (pintype "passive"))
      (node (ref "U3") (pin "12") (pinfunction "[STADC]/SCL/P1.3_12") (pintype "passive"))
    )
    (net (code "6") (name "/CLK_O") (class "Default")
      (node (ref "IC1") (pin "11") (pinfunction "SHCP_11") (pintype "passive"))
      (node (ref "U3") (pin "15") (pinfunction "PWM2/IC2/SPICLK/P1.0_15") (pintype "passive"))
    )
    (net (code "7") (name "/D0") (class "Default")
      (node (ref "Q1") (pin "3") (pinfunction "OUT_3") (pintype "passive"))
      (node (ref "Q12") (pin "3") (pinfunction "OUT_3") (pintype "passive"))
      (node (ref "Q21") (pin "3") (pinfunction "OUT_3") (pintype "passive"))
      (node (ref "Q30") (pin "3") (pinfunction "OUT_3") (pintype "passive"))
      (node (ref "Q39") (pin "3") (pinfunction "OUT_3") (pintype "passive"))
      (node (ref "Q48") (pin "3") (pinfunction "OUT_3") (pintype "passive"))
      (node (ref "Q57") (pin "3") (pinfunction "OUT_3") (pintype "passive"))
      (node (ref "Q66") (pin "3") (pinfunction "OUT_3") (pintype "passive"))
      (node (ref "R23") (pin "2") (pinfunction "2_2") (pintype "passive"))
    )
    (net (code "8") (name "/D1") (class "Default")
      (node (ref "Q13") (pin "3") (pinfunction "OUT_3") (pintype "passive"))
      (node (ref "Q2") (pin "3") (pinfunction "OUT_3") (pintype "passive"))
      (node (ref "Q22") (pin "3") (pinfunction "OUT_3") (pintype "passive"))
      (node (ref "Q31") (pin "3") (pinfunction "OUT_3") (pintype "passive"))
      (node (ref "Q40") (pin "3") (pinfunction "OUT_3") (pintype "passive"))
      (node (ref "Q49") (pin "3") (pinfunction "OUT_3") (pintype "passive"))
      (node (ref "Q58") (pin "3") (pinfunction "OUT_3") (pintype "passive"))
      (node (ref "Q67") (pin "3") (pinfunction "OUT_3") (pintype "passive"))
      (node (ref "R24") (pin "2") (pinfunction "2_2") (pintype "passive"))
    )
    (net (code "9") (name "/D2") (class "Default")
      (node (ref "Q14") (pin "3") (pinfunction "OUT_3") (pintype "passive"))
      (node (ref "Q23") (pin "3") (pinfunction "OUT_3") (pintype "passive"))
      (node (ref "Q3") (pin "3") (pinfunction "OUT_3") (pintype "passive"))
      (node (ref "Q32") (pin "3") (pinfunction "OUT_3") (pintype "passive"))
      (node (ref "Q41") (pin "3") (pinfunction "OUT_3") (pintype "passive"))
      (node (ref "Q50") (pin "3") (pinfunction "OUT_3") (pintype "passive"))
      (node (ref "Q59") (pin "3") (pinfunction "OUT_3") (pintype "passive"))
      (node (ref "Q68") (pin "3") (pinfunction "OUT_3") (pintype "passive"))
      (node (ref "R25") (pin "2") (pinfunction "2_2") (pintype "passive"))
    )
    (net (code "10") (name "/D3") (class "Default")
      (node (ref "Q15") (pin "3") (pinfunction "OUT_3") (pintype "passive"))
      (node (ref "Q24") (pin "3") (pinfunction "OUT_3") (pintype "passive"))
      (node (ref "Q33") (pin "3") (pinfunction "OUT_3") (pintype "passive"))
      (node (ref "Q4") (pin "3") (pinfunction "OUT_3") (pintype "passive"))
      (node (ref "Q42") (pin "3") (pinfunction "OUT_3") (pintype "passive"))
      (node (ref "Q51") (pin "3") (pinfunction "OUT_3") (pintype "passive"))
      (node (ref "Q60") (pin "3") (pinfunction "OUT_3") (pintype "passive"))
      (node (ref "Q69") (pin "3") (pinfunction "OUT_3") (pintype "passive"))
      (node (ref "R26") (pin "2") (pinfunction "2_2") (pintype "passive"))
    )
    (net (code "11") (name "/D4") (class "Default")
      (node (ref "Q16") (pin "3") (pinfunction "OUT_3") (pintype "passive"))
      (node (ref "Q25") (pin "3") (pinfunction "OUT_3") (pintype "passive"))
      (node (ref "Q34") (pin "3") (pinfunction "OUT_3") (pintype "passive"))
      (node (ref "Q43") (pin "3") (pinfunction "OUT_3") (pintype "passive"))
      (node (ref "Q5") (pin "3") (pinfunction "OUT_3") (pintype "passive"))
      (node (ref "Q52") (pin "3") (pinfunction "OUT_3") (pintype "passive"))
      (node (ref "Q61") (pin "3") (pinfunction "OUT_3") (pintype "passive"))
      (node (ref "Q70") (pin "3") (pinfunction "OUT_3") (pintype "passive"))
      (node (ref "R27") (pin "2") (pinfunction "2_2") (pintype "passive"))
    )
    (net (code "12") (name "/D5") (class "Default")
      (node (ref "Q17") (pin "3") (pinfunction "OUT_3") (pintype "passive"))
      (node (ref "Q26") (pin "3") (pinfunction "OUT_3") (pintype "passive"))
      (node (ref "Q35") (pin "3") (pinfunction "OUT_3") (pintype "passive"))
      (node (ref "Q44") (pin "3") (pinfunction "OUT_3") (pintype "passive"))
      (node (ref "Q53") (pin "3") (pinfunction "OUT_3") (pintype "passive"))
      (node (ref "Q6") (pin "3") (pinfunction "OUT_3") (pintype "passive"))
      (node (ref "Q62") (pin "3") (pinfunction "OUT_3") (pintype "passive"))
      (node (ref "Q71") (pin "3") (pinfunction "OUT_3") (pintype "passive"))
      (node (ref "R28") (pin "2") (pinfunction "2_2") (pintype "passive"))
    )
    (net (code "13") (name "/D6") (class "Default")
      (node (ref "Q18") (pin "3") (pinfunction "OUT_3") (pintype "passive"))
      (node (ref "Q27") (pin "3") (pinfunction "OUT_3") (pintype "passive"))
      (node (ref "Q36") (pin "3") (pinfunction "OUT_3") (pintype "passive"))
      (node (ref "Q45") (pin "3") (pinfunction "OUT_3") (pintype "passive"))
      (node (ref "Q54") (pin "3") (pinfunction "OUT_3") (pintype "passive"))
      (node (ref "Q63") (pin "3") (pinfunction "OUT_3") (pintype "passive"))
      (node (ref "Q7") (pin "3") (pinfunction "OUT_3") (pintype "passive"))
      (node (ref "Q72") (pin "3") (pinfunction "OUT_3") (pintype "passive"))
      (node (ref "R29") (pin "2") (pinfunction "2_2") (pintype "passive"))
    )
    (net (code "14") (name "/D7") (class "Default")
      (node (ref "Q19") (pin "3") (pinfunction "OUT_3") (pintype "passive"))
      (node (ref "Q28") (pin "3") (pinfunction "OUT_3") (pintype "passive"))
      (node (ref "Q37") (pin "3") (pinfunction "OUT_3") (pintype "passive"))
      (node (ref "Q46") (pin "3") (pinfunction "OUT_3") (pintype "passive"))
      (node (ref "Q55") (pin "3") (pinfunction "OUT_3") (pintype "passive"))
      (node (ref "Q64") (pin "3") (pinfunction "OUT_3") (pintype "passive"))
      (node (ref "Q73") (pin "3") (pinfunction "OUT_3") (pintype "passive"))
      (node (ref "Q8") (pin "3") (pinfunction "OUT_3") (pintype "passive"))
      (node (ref "R30") (pin "2") (pinfunction "2_2") (pintype "passive"))
    )
    (net (code "15") (name "/DAT_I") (class "Default")
      (node (ref "U2") (pin "9") (pinfunction "Q7_9") (pintype "passive"))
      (node (ref "U3") (pin "11") (pinfunction "SDA/FB/PWM1/P1.4_11") (pintype "passive"))
    )
    (net (code "16") (name "/DAT_O") (class "Default")
      (node (ref "IC1") (pin "14") (pinfunction "DS_14") (pintype "passive"))
      (node (ref "U3") (pin "14") (pinfunction "PWM1/IC1/AIN7/CLO/P1.1_14") (pintype "passive"))
    )
    (net (code "17") (name "/ICP_CLK") (class "Default")
      (node (ref "P2") (pin "4") (pinfunction "CLK_4") (pintype "passive"))
      (node (ref "U3") (pin "18") (pinfunction "P0.2/ICPCLK/RXD_1/[SCL]_18") (pintype "passive"))
    )
    (net (code "18") (name "/ICP_DA") (class "Default")
      (node (ref "P2") (pin "3") (pinfunction "DAT_3") (pintype "passive"))
      (node (ref "U3") (pin "8") (pinfunction "[SDA]/TXD_1/ICPDAT/P1.6_8") (pintype "passive"))
    )
    (net (code "19") (name "/LAT_I") (class "Default")
      (node (ref "U2") (pin "1") (pinfunction "~{PL}_1") (pintype "passive"))
      (node (ref "U3") (pin "10") (pinfunction "PWM5/IC7/~{SS}/P1.5_10") (pintype "passive"))
    )
    (net (code "20") (name "/LAT_O") (class "Default")
      (node (ref "IC1") (pin "12") (pinfunction "STCP_12") (pintype "passive"))
      (node (ref "U3") (pin "13") (pinfunction "PWM0/IC0/P1.2_13") (pintype "passive"))
    )
    (net (code "21") (name "/RST") (class "Default")
      (node (ref "P2") (pin "5") (pinfunction "~{RS}T_5") (pintype "passive"))
      (node (ref "R22") (pin "2") (pinfunction "2_2") (pintype "passive"))
      (node (ref "U3") (pin "4") (pinfunction "~{RST}/P2.0_4") (pintype "passive"))
    )
    (net (code "22") (name "/RX3.3V") (class "Default")
      (node (ref "P1") (pin "2") (pinfunction "2_2") (pintype "passive"))
      (node (ref "Q11") (pin "2") (pinfunction "S_2") (pintype "passive"))
      (node (ref "R6") (pin "1") (pinfunction "1_1") (pintype "passive"))
    )
    (net (code "23") (name "/RX5V") (class "Default")
      (node (ref "Q11") (pin "3") (pinfunction "D_3") (pintype "passive"))
      (node (ref "R3") (pin "1") (pinfunction "1_1") (pintype "passive"))
      (node (ref "U3") (pin "3") (pinfunction "P0.7/RXD/AIN2_3") (pintype "passive"))
    )
    (net (code "24") (name "/T1") (class "Default")
      (node (ref "Q9") (pin "1") (pinfunction "B_1") (pintype "passive"))
      (node (ref "R1") (pin "1") (pinfunction "1_1") (pintype "passive"))
      (node (ref "R10") (pin "1") (pinfunction "1_1") (pintype "passive"))
    )
    (net (code "25") (name "/T2") (class "Default")
      (node (ref "Q20") (pin "1") (pinfunction "B_1") (pintype "passive"))
      (node (ref "R11") (pin "1") (pinfunction "1_1") (pintype "passive"))
      (node (ref "R7") (pin "1") (pinfunction "1_1") (pintype "passive"))
    )
    (net (code "26") (name "/T3") (class "Default")
      (node (ref "Q29") (pin "1") (pinfunction "B_1") (pintype "passive"))
      (node (ref "R12") (pin "1") (pinfunction "1_1") (pintype "passive"))
      (node (ref "R8") (pin "1") (pinfunction "1_1") (pintype "passive"))
    )
    (net (code "27") (name "/T4") (class "Default")
      (node (ref "Q38") (pin "1") (pinfunction "B_1") (pintype "passive"))
      (node (ref "R13") (pin "1") (pinfunction "1_1") (pintype "passive"))
      (node (ref "R9") (pin "1") (pinfunction "1_1") (pintype "passive"))
    )
    (net (code "28") (name "/T5") (class "Default")
      (node (ref "Q47") (pin "1") (pinfunction "B_1") (pintype "passive"))
      (node (ref "R14") (pin "1") (pinfunction "1_1") (pintype "passive"))
      (node (ref "R15") (pin "1") (pinfunction "1_1") (pintype "passive"))
    )
    (net (code "29") (name "/T6") (class "Default")
      (node (ref "Q56") (pin "1") (pinfunction "B_1") (pintype "passive"))
      (node (ref "R16") (pin "1") (pinfunction "1_1") (pintype "passive"))
      (node (ref "R19") (pin "1") (pinfunction "1_1") (pintype "passive"))
    )
    (net (code "30") (name "/T7") (class "Default")
      (node (ref "Q65") (pin "1") (pinfunction "B_1") (pintype "passive"))
      (node (ref "R17") (pin "1") (pinfunction "1_1") (pintype "passive"))
      (node (ref "R20") (pin "1") (pinfunction "1_1") (pintype "passive"))
    )
    (net (code "31") (name "/T8") (class "Default")
      (node (ref "Q74") (pin "1") (pinfunction "B_1") (pintype "passive"))
      (node (ref "R18") (pin "1") (pinfunction "1_1") (pintype "passive"))
      (node (ref "R21") (pin "1") (pinfunction "1_1") (pintype "passive"))
    )
    (net (code "32") (name "/TX3.3V") (class "Default")
      (node (ref "P1") (pin "3") (pinfunction "3_3") (pintype "passive"))
      (node (ref "Q10") (pin "2") (pinfunction "S_2") (pintype "passive"))
      (node (ref "R5") (pin "1") (pinfunction "1_1") (pintype "passive"))
    )
    (net (code "33") (name "/TX5V") (class "Default")
      (node (ref "Q10") (pin "3") (pinfunction "D_3") (pintype "passive"))
      (node (ref "R2") (pin "1") (pinfunction "1_1") (pintype "passive"))
      (node (ref "U3") (pin "2") (pinfunction "P0.6/TXD/AIN3_2") (pintype "passive"))
    )
    (net (code "34") (name "GND") (class "Default")
      (node (ref "C1") (pin "2") (pinfunction "2_2") (pintype "passive"))
      (node (ref "C2") (pin "1") (pinfunction "1_1") (pintype "passive"))
      (node (ref "C3") (pin "2") (pinfunction "2_2") (pintype "passive"))
      (node (ref "C4") (pin "1") (pinfunction "1_1") (pintype "passive"))
      (node (ref "C5") (pin "1") (pinfunction "1_1") (pintype "passive"))
      (node (ref "C6") (pin "1") (pinfunction "1_1") (pintype "passive"))
      (node (ref "C7") (pin "2") (pinfunction "2_2") (pintype "passive"))
      (node (ref "C8") (pin "2") (pinfunction "2_2") (pintype "passive"))
      (node (ref "CN1") (pin "1") (pinfunction "-_1") (pintype "passive"))
      (node (ref "CN1") (pin "3") (pinfunction "3_3") (pintype "passive"))
      (node (ref "CN1") (pin "4") (pinfunction "4_4") (pintype "passive"))
      (node (ref "D3") (pin "1") (pinfunction "A_1") (pintype "passive"))
      (node (ref "IC1") (pin "13") (pinfunction "~{OE}_13") (pintype "passive"))
      (node (ref "IC1") (pin "8") (pinfunction "GND_8") (pintype "power_in"))
      (node (ref "L_PW1") (pin "2") (pinfunction "2_2") (pintype "passive"))
      (node (ref "P1") (pin "1") (pinfunction "1_1") (pintype "passive"))
      (node (ref "P2") (pin "6") (pinfunction "GND_6") (pintype "passive"))
      (node (ref "Q20") (pin "2") (pinfunction "E_2") (pintype "passive"))
      (node (ref "Q29") (pin "2") (pinfunction "E_2") (pintype "passive"))
      (node (ref "Q38") (pin "2") (pinfunction "E_2") (pintype "passive"))
      (node (ref "Q47") (pin "2") (pinfunction "E_2") (pintype "passive"))
      (node (ref "Q56") (pin "2") (pinfunction "E_2") (pintype "passive"))
      (node (ref "Q65") (pin "2") (pinfunction "E_2") (pintype "passive"))
      (node (ref "Q74") (pin "2") (pinfunction "E_2") (pintype "passive"))
      (node (ref "Q9") (pin "2") (pinfunction "E_2") (pintype "passive"))
      (node (ref "R1") (pin "2") (pinfunction "2_2") (pintype "passive"))
      (node (ref "R14") (pin "2") (pinfunction "2_2") (pintype "passive"))
      (node (ref "R19") (pin "2") (pinfunction "2_2") (pintype "passive"))
      (node (ref "R20") (pin "2") (pinfunction "2_2") (pintype "passive"))
      (node (ref "R21") (pin "2") (pinfunction "2_2") (pintype "passive"))
      (node (ref "R7") (pin "2") (pinfunction "2_2") (pintype "passive"))
      (node (ref "R8") (pin "2") (pinfunction "2_2") (pintype "passive"))
      (node (ref "R9") (pin "2") (pinfunction "2_2") (pintype "passive"))
      (node (ref "U1") (pin "3") (pinfunction "GND_3") (pintype "passive"))
      (node (ref "U1") (pin "5") (pinfunction "~{ON}/OFF_5") (pintype "passive"))
      (node (ref "U2") (pin "10") (pinfunction "DS_10") (pintype "passive"))
      (node (ref "U2") (pin "15") (pinfunction "~{CE}_15") (pintype "passive"))
      (node (ref "U2") (pin "8") (pinfunction "GND_8") (pintype "power_in"))
      (node (ref "U3") (pin "7") (pinfunction "GND_7") (pintype "passive"))
    )
    (net (code "35") (name "Net-(D3-K)") (class "Default")
      (node (ref "D3") (pin "2") (pinfunction "K_2") (pintype "passive"))
      (node (ref "L1") (pin "1") (pinfunction "1_1") (pintype "passive"))
      (node (ref "U1") (pin "2") (pinfunction "Vo_2") (pintype "passive"))
    )
    (net (code "36") (name "Net-(IC1-QA)") (class "Default")
      (node (ref "IC1") (pin "15") (pinfunction "QA_15") (pintype "passive"))
      (node (ref "R10") (pin "2") (pinfunction "2_2") (pintype "passive"))
    )
    (net (code "37") (name "Net-(IC1-QB)") (class "Default")
      (node (ref "IC1") (pin "1") (pinfunction "QB_1") (pintype "passive"))
      (node (ref "R11") (pin "2") (pinfunction "2_2") (pintype "passive"))
    )
    (net (code "38") (name "Net-(IC1-QC)") (class "Default")
      (node (ref "IC1") (pin "2") (pinfunction "QC_2") (pintype "passive"))
      (node (ref "R12") (pin "2") (pinfunction "2_2") (pintype "passive"))
    )
    (net (code "39") (name "Net-(IC1-QD)") (class "Default")
      (node (ref "IC1") (pin "3") (pinfunction "QD_3") (pintype "passive"))
      (node (ref "R13") (pin "2") (pinfunction "2_2") (pintype "passive"))
    )
    (net (code "40") (name "Net-(IC1-QE)") (class "Default")
      (node (ref "IC1") (pin "4") (pinfunction "QE_4") (pintype "passive"))
      (node (ref "R15") (pin "2") (pinfunction "2_2") (pintype "passive"))
    )
    (net (code "41") (name "Net-(IC1-QF)") (class "Default")
      (node (ref "IC1") (pin "5") (pinfunction "QF_5") (pintype "passive"))
      (node (ref "R16") (pin "2") (pinfunction "2_2") (pintype "passive"))
    )
    (net (code "42") (name "Net-(IC1-QG)") (class "Default")
      (node (ref "IC1") (pin "6") (pinfunction "QG_6") (pintype "passive"))
      (node (ref "R17") (pin "2") (pinfunction "2_2") (pintype "passive"))
    )
    (net (code "43") (name "Net-(IC1-QH)") (class "Default")
      (node (ref "IC1") (pin "7") (pinfunction "QH_7") (pintype "passive"))
      (node (ref "R18") (pin "2") (pinfunction "2_2") (pintype "passive"))
    )
    (net (code "44") (name "Net-(L_PW1-Pad1)") (class "Default")
      (node (ref "L_PW1") (pin "1") (pinfunction "1_1") (pintype "passive"))
      (node (ref "R4") (pin "2") (pinfunction "2_2") (pintype "passive"))
    )
    (net (code "45") (name "Net-(Q1-GND)") (class "Default")
      (node (ref "D1") (pin "2") (pinfunction "2_2") (pintype "passive"))
      (node (ref "Q1") (pin "2") (pinfunction "GND_2") (pintype "passive"))
      (node (ref "Q2") (pin "2") (pinfunction "GND_2") (pintype "passive"))
      (node (ref "Q3") (pin "2") (pinfunction "GND_2") (pintype "passive"))
      (node (ref "Q4") (pin "2") (pinfunction "GND_2") (pintype "passive"))
      (node (ref "Q5") (pin "2") (pinfunction "GND_2") (pintype "passive"))
      (node (ref "Q6") (pin "2") (pinfunction "GND_2") (pintype "passive"))
      (node (ref "Q7") (pin "2") (pinfunction "GND_2") (pintype "passive"))
      (node (ref "Q8") (pin "2") (pinfunction "GND_2") (pintype "passive"))
      (node (ref "Q9") (pin "3") (pinfunction "C_3") (pintype "passive"))
    )
    (net (code "46") (name "Net-(Q12-GND)") (class "Default")
      (node (ref "D4") (pin "2") (pinfunction "2_2") (pintype "passive"))
      (node (ref "Q12") (pin "2") (pinfunction "GND_2") (pintype "passive"))
      (node (ref "Q13") (pin "2") (pinfunction "GND_2") (pintype "passive"))
      (node (ref "Q14") (pin "2") (pinfunction "GND_2") (pintype "passive"))
      (node (ref "Q15") (pin "2") (pinfunction "GND_2") (pintype "passive"))
      (node (ref "Q16") (pin "2") (pinfunction "GND_2") (pintype "passive"))
      (node (ref "Q17") (pin "2") (pinfunction "GND_2") (pintype "passive"))
      (node (ref "Q18") (pin "2") (pinfunction "GND_2") (pintype "passive"))
      (node (ref "Q19") (pin "2") (pinfunction "GND_2") (pintype "passive"))
      (node (ref "Q20") (pin "3") (pinfunction "C_3") (pintype "passive"))
    )
    (net (code "47") (name "Net-(Q21-GND)") (class "Default")
      (node (ref "D5") (pin "2") (pinfunction "2_2") (pintype "passive"))
      (node (ref "Q21") (pin "2") (pinfunction "GND_2") (pintype "passive"))
      (node (ref "Q22") (pin "2") (pinfunction "GND_2") (pintype "passive"))
      (node (ref "Q23") (pin "2") (pinfunction "GND_2") (pintype "passive"))
      (node (ref "Q24") (pin "2") (pinfunction "GND_2") (pintype "passive"))
      (node (ref "Q25") (pin "2") (pinfunction "GND_2") (pintype "passive"))
      (node (ref "Q26") (pin "2") (pinfunction "GND_2") (pintype "passive"))
      (node (ref "Q27") (pin "2") (pinfunction "GND_2") (pintype "passive"))
      (node (ref "Q28") (pin "2") (pinfunction "GND_2") (pintype "passive"))
      (node (ref "Q29") (pin "3") (pinfunction "C_3") (pintype "passive"))
    )
    (net (code "48") (name "Net-(Q30-GND)") (class "Default")
      (node (ref "D6") (pin "2") (pinfunction "2_2") (pintype "passive"))
      (node (ref "Q30") (pin "2") (pinfunction "GND_2") (pintype "passive"))
      (node (ref "Q31") (pin "2") (pinfunction "GND_2") (pintype "passive"))
      (node (ref "Q32") (pin "2") (pinfunction "GND_2") (pintype "passive"))
      (node (ref "Q33") (pin "2") (pinfunction "GND_2") (pintype "passive"))
      (node (ref "Q34") (pin "2") (pinfunction "GND_2") (pintype "passive"))
      (node (ref "Q35") (pin "2") (pinfunction "GND_2") (pintype "passive"))
      (node (ref "Q36") (pin "2") (pinfunction "GND_2") (pintype "passive"))
      (node (ref "Q37") (pin "2") (pinfunction "GND_2") (pintype "passive"))
      (node (ref "Q38") (pin "3") (pinfunction "C_3") (pintype "passive"))
    )
    (net (code "49") (name "Net-(Q39-GND)") (class "Default")
      (node (ref "D7") (pin "2") (pinfunction "2_2") (pintype "passive"))
      (node (ref "Q39") (pin "2") (pinfunction "GND_2") (pintype "passive"))
      (node (ref "Q40") (pin "2") (pinfunction "GND_2") (pintype "passive"))
      (node (ref "Q41") (pin "2") (pinfunction "GND_2") (pintype "passive"))
      (node (ref "Q42") (pin "2") (pinfunction "GND_2") (pintype "passive"))
      (node (ref "Q43") (pin "2") (pinfunction "GND_2") (pintype "passive"))
      (node (ref "Q44") (pin "2") (pinfunction "GND_2") (pintype "passive"))
      (node (ref "Q45") (pin "2") (pinfunction "GND_2") (pintype "passive"))
      (node (ref "Q46") (pin "2") (pinfunction "GND_2") (pintype "passive"))
      (node (ref "Q47") (pin "3") (pinfunction "C_3") (pintype "passive"))
    )
    (net (code "50") (name "Net-(Q48-GND)") (class "Default")
      (node (ref "D8") (pin "2") (pinfunction "2_2") (pintype "passive"))
      (node (ref "Q48") (pin "2") (pinfunction "GND_2") (pintype "passive"))
      (node (ref "Q49") (pin "2") (pinfunction "GND_2") (pintype "passive"))
      (node (ref "Q50") (pin "2") (pinfunction "GND_2") (pintype "passive"))
      (node (ref "Q51") (pin "2") (pinfunction "GND_2") (pintype "passive"))
      (node (ref "Q52") (pin "2") (pinfunction "GND_2") (pintype "passive"))
      (node (ref "Q53") (pin "2") (pinfunction "GND_2") (pintype "passive"))
      (node (ref "Q54") (pin "2") (pinfunction "GND_2") (pintype "passive"))
      (node (ref "Q55") (pin "2") (pinfunction "GND_2") (pintype "passive"))
      (node (ref "Q56") (pin "3") (pinfunction "C_3") (pintype "passive"))
    )
    (net (code "51") (name "Net-(Q57-GND)") (class "Default")
      (node (ref "D9") (pin "2") (pinfunction "2_2") (pintype "passive"))
      (node (ref "Q57") (pin "2") (pinfunction "GND_2") (pintype "passive"))
      (node (ref "Q58") (pin "2") (pinfunction "GND_2") (pintype "passive"))
      (node (ref "Q59") (pin "2") (pinfunction "GND_2") (pintype "passive"))
      (node (ref "Q60") (pin "2") (pinfunction "GND_2") (pintype "passive"))
      (node (ref "Q61") (pin "2") (pinfunction "GND_2") (pintype "passive"))
      (node (ref "Q62") (pin "2") (pinfunction "GND_2") (pintype "passive"))
      (node (ref "Q63") (pin "2") (pinfunction "GND_2") (pintype "passive"))
      (node (ref "Q64") (pin "2") (pinfunction "GND_2") (pintype "passive"))
      (node (ref "Q65") (pin "3") (pinfunction "C_3") (pintype "passive"))
    )
    (net (code "52") (name "Net-(Q66-GND)") (class "Default")
      (node (ref "D10") (pin "2") (pinfunction "2_2") (pintype "passive"))
      (node (ref "Q66") (pin "2") (pinfunction "GND_2") (pintype "passive"))
      (node (ref "Q67") (pin "2") (pinfunction "GND_2") (pintype "passive"))
      (node (ref "Q68") (pin "2") (pinfunction "GND_2") (pintype "passive"))
      (node (ref "Q69") (pin "2") (pinfunction "GND_2") (pintype "passive"))
      (node (ref "Q70") (pin "2") (pinfunction "GND_2") (pintype "passive"))
      (node (ref "Q71") (pin "2") (pinfunction "GND_2") (pintype "passive"))
      (node (ref "Q72") (pin "2") (pinfunction "GND_2") (pintype "passive"))
      (node (ref "Q73") (pin "2") (pinfunction "GND_2") (pintype "passive"))
      (node (ref "Q74") (pin "3") (pinfunction "C_3") (pintype "passive"))
    )
    (net (code "53") (name "Net-(U2-D0)") (class "Default")
      (node (ref "R23") (pin "1") (pinfunction "1_1") (pintype "passive"))
      (node (ref "U2") (pin "11") (pinfunction "D0_11") (pintype "passive"))
    )
    (net (code "54") (name "Net-(U2-D1)") (class "Default")
      (node (ref "R24") (pin "1") (pinfunction "1_1") (pintype "passive"))
      (node (ref "U2") (pin "12") (pinfunction "D1_12") (pintype "passive"))
    )
    (net (code "55") (name "Net-(U2-D2)") (class "Default")
      (node (ref "R25") (pin "1") (pinfunction "1_1") (pintype "passive"))
      (node (ref "U2") (pin "13") (pinfunction "D2_13") (pintype "passive"))
    )
    (net (code "56") (name "Net-(U2-D3)") (class "Default")
      (node (ref "R26") (pin "1") (pinfunction "1_1") (pintype "passive"))
      (node (ref "U2") (pin "14") (pinfunction "D3_14") (pintype "passive"))
    )
    (net (code "57") (name "Net-(U2-D4)") (class "Default")
      (node (ref "R27") (pin "1") (pinfunction "1_1") (pintype "passive"))
      (node (ref "U2") (pin "3") (pinfunction "D4_3") (pintype "passive"))
    )
    (net (code "58") (name "Net-(U2-D5)") (class "Default")
      (node (ref "R28") (pin "1") (pinfunction "1_1") (pintype "passive"))
      (node (ref "U2") (pin "4") (pinfunction "D5_4") (pintype "passive"))
    )
    (net (code "59") (name "Net-(U2-D6)") (class "Default")
      (node (ref "R29") (pin "1") (pinfunction "1_1") (pintype "passive"))
      (node (ref "U2") (pin "5") (pinfunction "D6_5") (pintype "passive"))
    )
    (net (code "60") (name "Net-(U2-D7)") (class "Default")
      (node (ref "R30") (pin "1") (pinfunction "1_1") (pintype "passive"))
      (node (ref "U2") (pin "6") (pinfunction "D7_6") (pintype "passive"))
    )
    (net (code "61") (name "unconnected-(IC1-QH'-Pad9)") (class "Default")
      (node (ref "IC1") (pin "9") (pinfunction "QH'_9") (pintype "passive"))
    )
    (net (code "62") (name "unconnected-(U2-~{Q7}-Pad7)") (class "Default")
      (node (ref "U2") (pin "7") (pinfunction "~{Q7}_7") (pintype "passive"))
    )
    (net (code "63") (name "unconnected-(U3-AIN0{slash}~{INT1}{slash}P1.7-Pad6)") (class "Default")
      (node (ref "U3") (pin "6") (pinfunction "AIN0/~{INT1}/P1.7_6") (pintype "passive"))
    )
    (net (code "64") (name "unconnected-(U3-P0.0{slash}PWM3{slash}IC3{slash}MOSI{slash}T1-Pad16)") (class "Default")
      (node (ref "U3") (pin "16") (pinfunction "P0.0/PWM3/IC3/MOSI/T1_16") (pintype "passive"))
    )
    (net (code "65") (name "unconnected-(U3-P0.1{slash}PWM4{slash}IC4{slash}MISO-Pad17)") (class "Default")
      (node (ref "U3") (pin "17") (pinfunction "P0.1/PWM4/IC4/MISO_17") (pintype "passive"))
    )
    (net (code "66") (name "unconnected-(U3-P0.3{slash}PWM5{slash}IC5{slash}AIN6-Pad19)") (class "Default")
      (node (ref "U3") (pin "19") (pinfunction "P0.3/PWM5/IC5/AIN6_19") (pintype "passive"))
    )
    (net (code "67") (name "unconnected-(U3-P0.4{slash}AIN5{slash}STADC{slash}PWM3{slash}IC3-Pad20)") (class "Default")
      (node (ref "U3") (pin "20") (pinfunction "P0.4/AIN5/STADC/PWM3/IC3_20") (pintype "passive"))
    )
    (net (code "68") (name "unconnected-(U3-P0.5{slash}PWM2{slash}IC6{slash}T0{slash}AIN4-Pad1)") (class "Default")
      (node (ref "U3") (pin "1") (pinfunction "P0.5/PWM2/IC6/T0/AIN4_1") (pintype "passive"))
    )
    (net (code "69") (name "unconnected-(U3-~{INT0}{slash}OSCIN{slash}AIN1{slash}P3.0-Pad5)") (class "Default")
      (node (ref "U3") (pin "5") (pinfunction "~{INT0}/OSCIN/AIN1/P3.0_5") (pintype "passive"))
    )
  )
)
